# 2228_Recepteur_MIKROE_NRF.net
KiCad netlist of a schematic drawn in Altium Designer
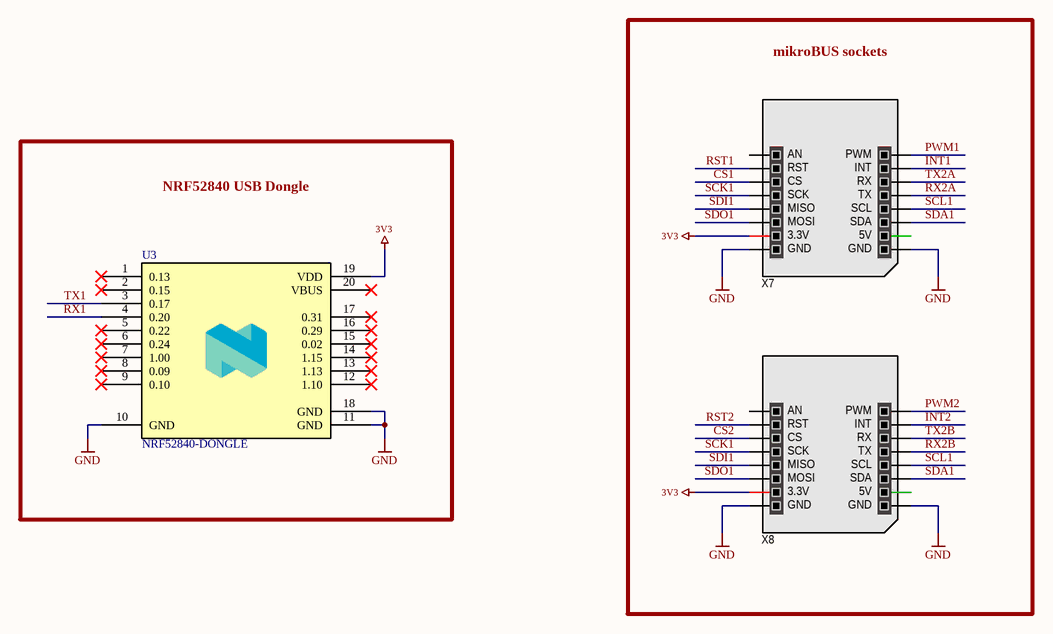
[diagram p0: 2228_Recepteur_MIKROE_NRF.SchDoc]

(export (version "E")
  (design (tool "Eeschema 10.0.6"))
  (components
    (comp (ref "U3")
      (value "NRF52840-DONGLE")
      (footprint "NRF52840_DONGLE")
      (fields (field (name "MANUFACTURER") "Nordic Semiconductor"))
      (libsource (lib "2228_AlarmeFenetre_Symbols") (part "NRF52840-DONGLE"))
    )
    (comp (ref "X7")
      (value "MIKROBUS HOST CONN TH 16")
      (footprint "MIKROBUS HOST CONN. TH")
      (libsource (lib "2228_AlarmeFenetre_Symbols") (part "MIKROBUS HOST CONN"))
    )
    (comp (ref "X8")
      (value "MIKROBUS HOST CONN TH 16")
      (footprint "MIKROBUS HOST CONN. TH")
      (libsource (lib "2228_AlarmeFenetre_Symbols") (part "MIKROBUS HOST CONN"))
    )
  )
  (nets
    (net (code "1") (name "/CS1") (class "Default")
      (node (ref "X7") (pin "3") (pinfunction "CS_3") (pintype "passive"))
    )
    (net (code "2") (name "/CS2") (class "Default")
      (node (ref "X8") (pin "3") (pinfunction "CS_3") (pintype "passive"))
    )
    (net (code "3") (name "/INT1") (class "Default")
      (node (ref "X7") (pin "15") (pinfunction "INT_15") (pintype "passive"))
    )
    (net (code "4") (name "/INT2") (class "Default")
      (node (ref "X8") (pin "15") (pinfunction "INT_15") (pintype "passive"))
    )
    (net (code "5") (name "/PWM1") (class "Default")
      (node (ref "X7") (pin "16") (pinfunction "PWM_16") (pintype "passive"))
    )
    (net (code "6") (name "/PWM2") (class "Default")
      (node (ref "X8") (pin "16") (pinfunction "PWM_16") (pintype "passive"))
    )
    (net (code "7") (name "/RST1") (class "Default")
      (node (ref "X7") (pin "2") (pinfunction "RST_2") (pintype "passive"))
    )
    (net (code "8") (name "/RST2") (class "Default")
      (node (ref "X8") (pin "2") (pinfunction "RST_2") (pintype "passive"))
    )
    (net (code "9") (name "/RX1") (class "Default")
      (node (ref "U3") (pin "4") (pinfunction "0.20_4") (pintype "passive"))
    )
    (net (code "10") (name "/RX2A") (class "Default")
      (node (ref "X7") (pin "13") (pinfunction "TX_13") (pintype "passive"))
    )
    (net (code "11") (name "/RX2B") (class "Default")
      (node (ref "X8") (pin "13") (pinfunction "TX_13") (pintype "passive"))
    )
    (net (code "12") (name "/SCK1") (class "Default")
      (node (ref "X7") (pin "4") (pinfunction "SCK_4") (pintype "passive"))
      (node (ref "X8") (pin "4") (pinfunction "SCK_4") (pintype "passive"))
    )
    (net (code "13") (name "/SCL1") (class "Default")
      (node (ref "X7") (pin "12") (pinfunction "SCL_12") (pintype "passive"))
      (node (ref "X8") (pin "12") (pinfunction "SCL_12") (pintype "passive"))
    )
    (net (code "14") (name "/SDA1") (class "Default")
      (node (ref "X7") (pin "11") (pinfunction "SDA_11") (pintype "passive"))
      (node (ref "X8") (pin "11") (pinfunction "SDA_11") (pintype "passive"))
    )
    (net (code "15") (name "/SDI1") (class "Default")
      (node (ref "X7") (pin "5") (pinfunction "MISO_5") (pintype "passive"))
      (node (ref "X8") (pin "5") (pinfunction "MISO_5") (pintype "passive"))
    )
    (net (code "16") (name "/SDO1") (class "Default")
      (node (ref "X7") (pin "6") (pinfunction "MOSI_6") (pintype "passive"))
      (node (ref "X8") (pin "6") (pinfunction "MOSI_6") (pintype "passive"))
    )
    (net (code "17") (name "/TX1") (class "Default")
      (node (ref "U3") (pin "3") (pinfunction "0.17_3") (pintype "passive"))
    )
    (net (code "18") (name "/TX2A") (class "Default")
      (node (ref "X7") (pin "14") (pinfunction "RX_14") (pintype "passive"))
    )
    (net (code "19") (name "/TX2B") (class "Default")
      (node (ref "X8") (pin "14") (pinfunction "RX_14") (pintype "passive"))
    )
    (net (code "20") (name "3V3") (class "Default")
      (node (ref "U3") (pin "19") (pinfunction "VDD_19") (pintype "passive"))
      (node (ref "X7") (pin "7") (pinfunction "3.3V_7") (pintype "passive"))
      (node (ref "X8") (pin "7") (pinfunction "3.3V_7") (pintype "passive"))
    )
    (net (code "21") (name "GND") (class "Default")
      (node (ref "U3") (pin "10") (pinfunction "GND_10") (pintype "passive"))
      (node (ref "U3") (pin "11") (pinfunction "GND_11") (pintype "passive"))
      (node (ref "U3") (pin "18") (pinfunction "GND_18") (pintype "passive"))
      (node (ref "X7") (pin "8") (pinfunction "GND_8") (pintype "passive"))
      (node (ref "X7") (pin "9") (pinfunction "GND_9") (pintype "passive"))
      (node (ref "X8") (pin "8") (pinfunction "GND_8") (pintype "passive"))
      (node (ref "X8") (pin "9") (pinfunction "GND_9") (pintype "passive"))
    )
    (net (code "22") (name "unconnected-(U3-0.02-Pad15)") (class "Default")
      (node (ref "U3") (pin "15") (pinfunction "0.02_15") (pintype "passive+no_connect"))
    )
    (net (code "23") (name "unconnected-(U3-0.09-Pad8)") (class "Default")
      (node (ref "U3") (pin "8") (pinfunction "0.09_8") (pintype "passive+no_connect"))
    )
    (net (code "24") (name "unconnected-(U3-0.10-Pad9)") (class "Default")
      (node (ref "U3") (pin "9") (pinfunction "0.10_9") (pintype "passive+no_connect"))
    )
    (net (code "25") (name "unconnected-(U3-0.13-Pad1)") (class "Default")
      (node (ref "U3") (pin "1") (pinfunction "0.13_1") (pintype "passive+no_connect"))
    )
    (net (code "26") (name "unconnected-(U3-0.15-Pad2)") (class "Default")
      (node (ref "U3") (pin "2") (pinfunction "0.15_2") (pintype "passive+no_connect"))
    )
    (net (code "27") (name "unconnected-(U3-0.22-Pad5)") (class "Default")
      (node (ref "U3") (pin "5") (pinfunction "0.22_5") (pintype "passive+no_connect"))
    )
    (net (code "28") (name "unconnected-(U3-0.24-Pad6)") (class "Default")
      (node (ref "U3") (pin "6") (pinfunction "0.24_6") (pintype "passive+no_connect"))
    )
    (net (code "29") (name "unconnected-(U3-0.29-Pad16)") (class "Default")
      (node (ref "U3") (pin "16") (pinfunction "0.29_16") (pintype "passive+no_connect"))
    )
    (net (code "30") (name "unconnected-(U3-0.31-Pad17)") (class "Default")
      (node (ref "U3") (pin "17") (pinfunction "0.31_17") (pintype "passive+no_connect"))
    )
    (net (code "31") (name "unconnected-(U3-1.00-Pad7)") (class "Default")
      (node (ref "U3") (pin "7") (pinfunction "1.00_7") (pintype "passive+no_connect"))
    )
    (net (code "32") (name "unconnected-(U3-1.10-Pad12)") (class "Default")
      (node (ref "U3") (pin "12") (pinfunction "1.10_12") (pintype "passive+no_connect"))
    )
    (net (code "33") (name "unconnected-(U3-1.13-Pad13)") (class "Default")
      (node (ref "U3") (pin "13") (pinfunction "1.13_13") (pintype "passive+no_connect"))
    )
    (net (code "34") (name "unconnected-(U3-1.15-Pad14)") (class "Default")
      (node (ref "U3") (pin "14") (pinfunction "1.15_14") (pintype "passive+no_connect"))
    )
    (net (code "35") (name "unconnected-(U3-VBUS-Pad20)") (class "Default")
      (node (ref "U3") (pin "20") (pinfunction "VBUS_20") (pintype "passive+no_connect"))
    )
    (net (code "36") (name "unconnected-(X7-5V-Pad10)") (class "Default")
      (node (ref "X7") (pin "10") (pinfunction "5V_10") (pintype "passive"))
    )
    (net (code "37") (name "unconnected-(X7-AN-Pad1)") (class "Default")
      (node (ref "X7") (pin "1") (pinfunction "AN_1") (pintype "passive"))
    )
    (net (code "38") (name "unconnected-(X8-5V-Pad10)") (class "Default")
      (node (ref "X8") (pin "10") (pinfunction "5V_10") (pintype "passive"))
    )
    (net (code "39") (name "unconnected-(X8-AN-Pad1)") (class "Default")
      (node (ref "X8") (pin "1") (pinfunction "AN_1") (pintype "passive"))
    )
  )
)
